# USB_SERIAL_QUAD.net
KiCad netlist of a schematic drawn in Altium Designer
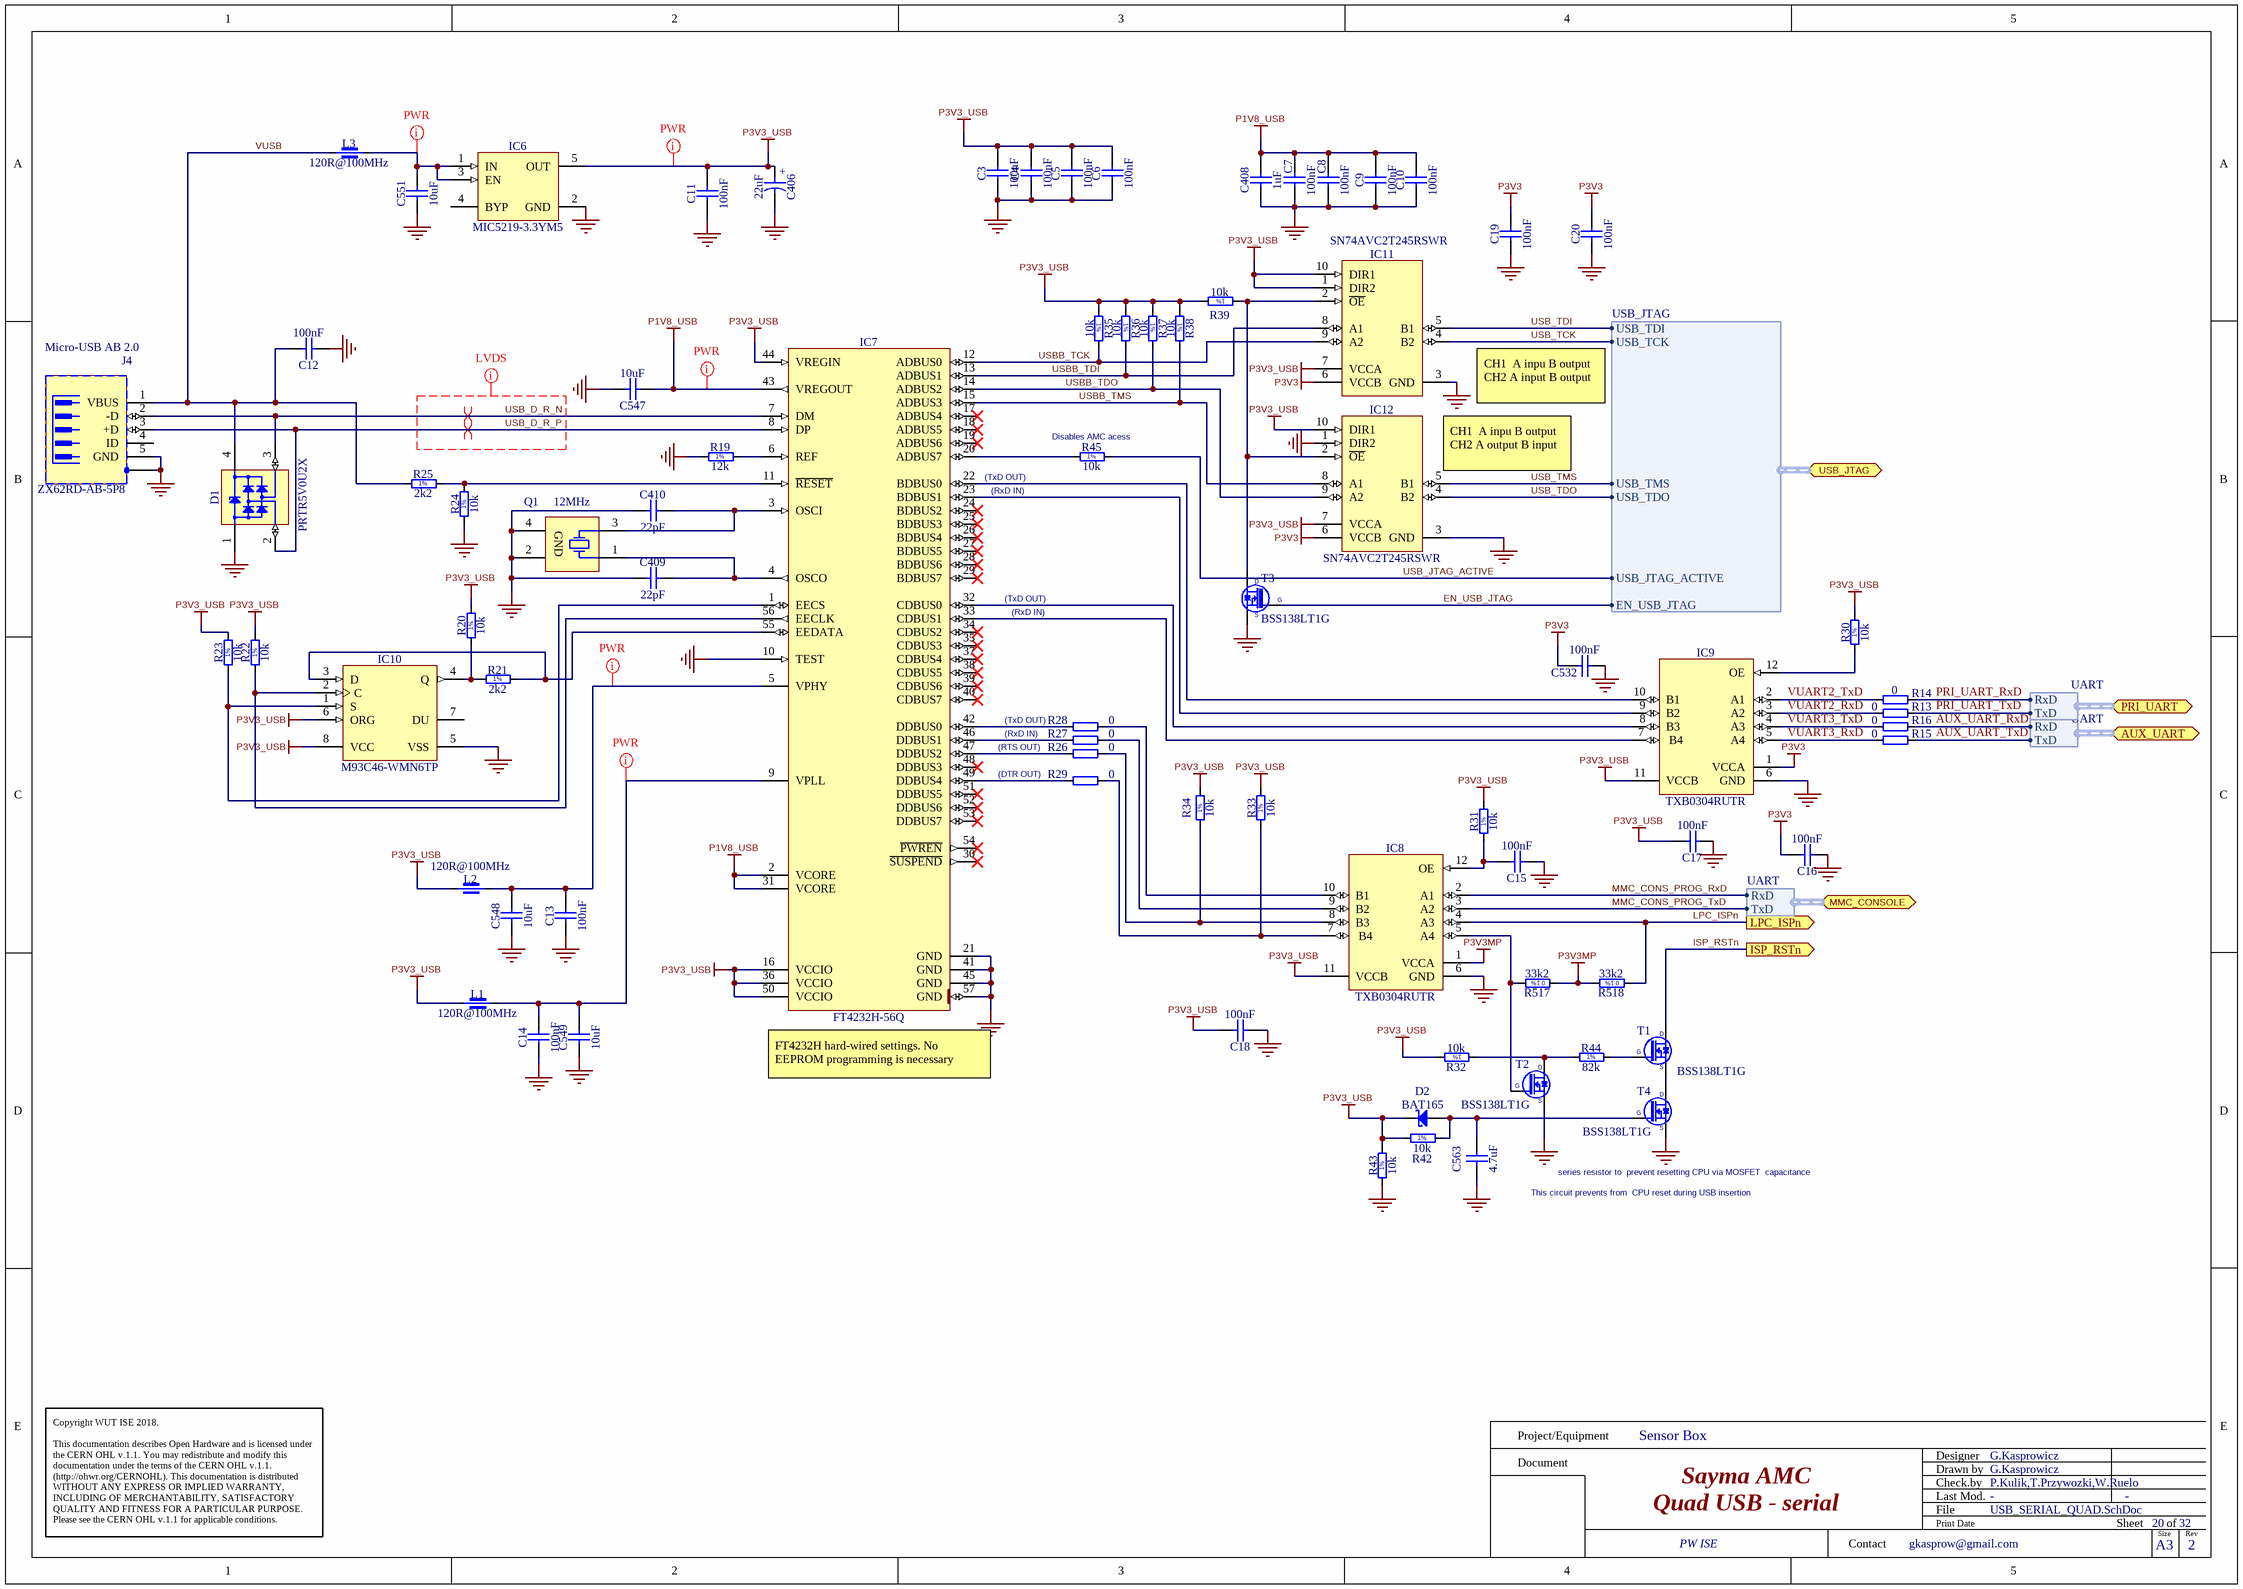
[diagram p0: USB_SERIAL_QUAD.SchDoc]

(export (version "E")
  (design (tool "Eeschema 10.0.6"))
  (components
    (comp (ref "C3")
      (value "100nF")
      (footprint "CAPC0603X33N")
      (description "Non-polarised capacitor")
      (fields
        (field (name "MANUFACTURER PART NUMBER") "CC0201_100NF_6.3V_10%_X5R")
        (field (name "MANUFACTURER") "GENERIC")
        (field (name "AUTHOR") "CERN DEM JLC")
      )
      (libsource (lib "Capacitors") (part "Capacitor - non polarized"))
    )
    (comp (ref "C4")
      (value "100nF")
      (footprint "CAPC0603X33N")
      (description "Non-polarised capacitor")
      (fields
        (field (name "MANUFACTURER PART NUMBER") "CC0201_100NF_6.3V_10%_X5R")
        (field (name "MANUFACTURER") "GENERIC")
        (field (name "AUTHOR") "CERN DEM JLC")
      )
      (libsource (lib "Capacitors") (part "Capacitor - non polarized"))
    )
    (comp (ref "C5")
      (value "100nF")
      (footprint "CAPC0603X33N")
      (description "Non-polarised capacitor")
      (fields
        (field (name "MANUFACTURER PART NUMBER") "CC0201_100NF_6.3V_10%_X5R")
        (field (name "MANUFACTURER") "GENERIC")
        (field (name "AUTHOR") "CERN DEM JLC")
      )
      (libsource (lib "Capacitors") (part "Capacitor - non polarized"))
    )
    (comp (ref "C6")
      (value "100nF")
      (footprint "CAPC0603X33N")
      (description "Non-polarised capacitor")
      (fields
        (field (name "MANUFACTURER PART NUMBER") "CC0201_100NF_6.3V_10%_X5R")
        (field (name "MANUFACTURER") "GENERIC")
        (field (name "AUTHOR") "CERN DEM JLC")
      )
      (libsource (lib "Capacitors") (part "Capacitor - non polarized"))
    )
    (comp (ref "C7")
      (value "100nF")
      (footprint "CAPC0603X33N")
      (description "Non-polarised capacitor")
      (fields
        (field (name "MANUFACTURER PART NUMBER") "CC0201_100NF_6.3V_10%_X5R")
        (field (name "MANUFACTURER") "GENERIC")
        (field (name "AUTHOR") "CERN DEM JLC")
      )
      (libsource (lib "Capacitors") (part "Capacitor - non polarized"))
    )
    (comp (ref "C8")
      (value "100nF")
      (footprint "CAPC0603X33N")
      (description "Non-polarised capacitor")
      (fields
        (field (name "MANUFACTURER PART NUMBER") "CC0201_100NF_6.3V_10%_X5R")
        (field (name "MANUFACTURER") "GENERIC")
        (field (name "AUTHOR") "CERN DEM JLC")
      )
      (libsource (lib "Capacitors") (part "Capacitor - non polarized"))
    )
    (comp (ref "C9")
      (value "100nF")
      (footprint "CAPC0603X33N")
      (description "Non-polarised capacitor")
      (fields
        (field (name "MANUFACTURER PART NUMBER") "CC0201_100NF_6.3V_10%_X5R")
        (field (name "MANUFACTURER") "GENERIC")
        (field (name "AUTHOR") "CERN DEM JLC")
      )
      (libsource (lib "Capacitors") (part "Capacitor - non polarized"))
    )
    (comp (ref "C10")
      (value "100nF")
      (footprint "CAPC0603X33N")
      (description "Non-polarised capacitor")
      (fields
        (field (name "MANUFACTURER PART NUMBER") "CC0201_100NF_6.3V_10%_X5R")
        (field (name "MANUFACTURER") "GENERIC")
        (field (name "AUTHOR") "CERN DEM JLC")
      )
      (libsource (lib "Capacitors") (part "Capacitor - non polarized"))
    )
    (comp (ref "C11")
      (value "100nF")
      (footprint "CAPC0603X33N")
      (description "Non-polarised capacitor")
      (fields
        (field (name "MANUFACTURER PART NUMBER") "CC0201_100NF_6.3V_10%_X5R")
        (field (name "MANUFACTURER") "GENERIC")
        (field (name "AUTHOR") "CERN DEM JLC")
      )
      (libsource (lib "Capacitors") (part "Capacitor - non polarized"))
    )
    (comp (ref "C12")
      (value "100nF")
      (footprint "CAPC0603X33N")
      (description "Non-polarised capacitor")
      (fields
        (field (name "MANUFACTURER PART NUMBER") "CC0201_100NF_6.3V_10%_X5R")
        (field (name "MANUFACTURER") "GENERIC")
        (field (name "AUTHOR") "CERN DEM JLC")
      )
      (libsource (lib "Capacitors") (part "Capacitor - non polarized"))
    )
    (comp (ref "C13")
      (value "100nF")
      (footprint "CAPC0603X33N")
      (description "Non-polarised capacitor")
      (fields
        (field (name "MANUFACTURER PART NUMBER") "CC0201_100NF_6.3V_10%_X5R")
        (field (name "MANUFACTURER") "GENERIC")
        (field (name "AUTHOR") "CERN DEM JLC")
      )
      (libsource (lib "Capacitors") (part "Capacitor - non polarized"))
    )
    (comp (ref "C14")
      (value "100nF")
      (footprint "CAPC0603X33N")
      (description "Non-polarised capacitor")
      (fields
        (field (name "MANUFACTURER PART NUMBER") "CC0201_100NF_6.3V_10%_X5R")
        (field (name "MANUFACTURER") "GENERIC")
        (field (name "AUTHOR") "CERN DEM JLC")
      )
      (libsource (lib "Capacitors") (part "Capacitor - non polarized"))
    )
    (comp (ref "C15")
      (value "100nF")
      (footprint "CAPC0603X33N")
      (description "Non-polarised capacitor")
      (fields
        (field (name "MANUFACTURER PART NUMBER") "CC0201_100NF_6.3V_10%_X5R")
        (field (name "MANUFACTURER") "GENERIC")
        (field (name "AUTHOR") "CERN DEM JLC")
      )
      (libsource (lib "Capacitors") (part "Capacitor - non polarized"))
    )
    (comp (ref "C16")
      (value "100nF")
      (footprint "CAPC0603X33N")
      (description "Non-polarised capacitor")
      (fields
        (field (name "MANUFACTURER PART NUMBER") "CC0201_100NF_6.3V_10%_X5R")
        (field (name "MANUFACTURER") "GENERIC")
        (field (name "AUTHOR") "CERN DEM JLC")
      )
      (libsource (lib "Capacitors") (part "Capacitor - non polarized"))
    )
    (comp (ref "C17")
      (value "100nF")
      (footprint "CAPC0603X33N")
      (description "Non-polarised capacitor")
      (fields
        (field (name "MANUFACTURER PART NUMBER") "CC0201_100NF_6.3V_10%_X5R")
        (field (name "MANUFACTURER") "GENERIC")
        (field (name "AUTHOR") "CERN DEM JLC")
      )
      (libsource (lib "Capacitors") (part "Capacitor - non polarized"))
    )
    (comp (ref "C18")
      (value "100nF")
      (footprint "CAPC0603X33N")
      (description "Non-polarised capacitor")
      (fields
        (field (name "MANUFACTURER PART NUMBER") "CC0201_100NF_6.3V_10%_X5R")
        (field (name "MANUFACTURER") "GENERIC")
        (field (name "AUTHOR") "CERN DEM JLC")
      )
      (libsource (lib "Capacitors") (part "Capacitor - non polarized"))
    )
    (comp (ref "C19")
      (value "100nF")
      (footprint "CAPC0603X33N")
      (description "Non-polarised capacitor")
      (fields
        (field (name "MANUFACTURER PART NUMBER") "CC0201_100NF_6.3V_10%_X5R")
        (field (name "MANUFACTURER") "GENERIC")
        (field (name "AUTHOR") "CERN DEM JLC")
      )
      (libsource (lib "Capacitors") (part "Capacitor - non polarized"))
    )
    (comp (ref "C20")
      (value "100nF")
      (footprint "CAPC0603X33N")
      (description "Non-polarised capacitor")
      (fields
        (field (name "MANUFACTURER PART NUMBER") "CC0201_100NF_6.3V_10%_X5R")
        (field (name "MANUFACTURER") "GENERIC")
        (field (name "AUTHOR") "CERN DEM JLC")
      )
      (libsource (lib "Capacitors") (part "Capacitor - non polarized"))
    )
    (comp (ref "C406")
      (value "22uF")
      (footprint "CAPMP3216X180N")
      (description "Polarised capacitor")
      (fields
        (field (name "MANUFACTURER PART NUMBER") "CTE3216-18_22UF_6.3V_10%_LESR0900")
        (field (name "MANUFACTURER") "GENERIC")
        (field (name "AUTHOR") "CERN DEM JLC")
      )
      (libsource (lib "Capacitors") (part "Capacitor - polarized"))
    )
    (comp (ref "C408")
      (value "1uF")
      (footprint "CAPC1005X55N")
      (description "Non-polarised capacitor")
      (fields
        (field (name "MANUFACTURER PART NUMBER") "CC0402_1UF_16V_10%_X5R")
        (field (name "MANUFACTURER") "GENERIC")
        (field (name "AUTHOR") "CERN DEM JLC")
      )
      (libsource (lib "Capacitors") (part "Capacitor - non polarized"))
    )
    (comp (ref "C409")
      (value "22pF")
      (footprint "CAPC1005X55N")
      (description "Non-polarised capacitor")
      (fields
        (field (name "MANUFACTURER PART NUMBER") "CC0402_22PF_50V_5%_C0G")
        (field (name "MANUFACTURER") "GENERIC")
        (field (name "AUTHOR") "CERN DEM JLC")
      )
      (libsource (lib "Capacitors") (part "Capacitor - non polarized"))
    )
    (comp (ref "C410")
      (value "22pF")
      (footprint "CAPC1005X55N")
      (description "Non-polarised capacitor")
      (fields
        (field (name "MANUFACTURER PART NUMBER") "CC0402_22PF_50V_5%_C0G")
        (field (name "MANUFACTURER") "GENERIC")
        (field (name "AUTHOR") "CERN DEM JLC")
      )
      (libsource (lib "Capacitors") (part "Capacitor - non polarized"))
    )
    (comp (ref "C532")
      (value "100nF")
      (footprint "CAPC0603X33N")
      (description "Non-polarised capacitor")
      (fields
        (field (name "MANUFACTURER PART NUMBER") "CC0201_100NF_6.3V_10%_X5R")
        (field (name "MANUFACTURER") "GENERIC")
        (field (name "AUTHOR") "CERN DEM JLC")
      )
      (libsource (lib "Capacitors") (part "Capacitor - non polarized"))
    )
    (comp (ref "C547")
      (value "10uF")
      (footprint "CAPC1608X87N")
      (description "Non-polarised capacitor")
      (fields
        (field (name "MANUFACTURER PART NUMBER") "CC0603_10uF_6.3V_20%_X5R")
        (field (name "MANUFACTURER") "GENERIC")
        (field (name "AUTHOR") "CERN DEM JLC")
      )
      (libsource (lib "Capacitors") (part "Capacitor - non polarized"))
    )
    (comp (ref "C548")
      (value "10uF")
      (footprint "CAPC1608X87N")
      (description "Non-polarised capacitor")
      (fields
        (field (name "MANUFACTURER PART NUMBER") "CC0603_10uF_6.3V_20%_X5R")
        (field (name "MANUFACTURER") "GENERIC")
        (field (name "AUTHOR") "CERN DEM JLC")
      )
      (libsource (lib "Capacitors") (part "Capacitor - non polarized"))
    )
    (comp (ref "C549")
      (value "10uF")
      (footprint "CAPC1608X87N")
      (description "Non-polarised capacitor")
      (fields
        (field (name "MANUFACTURER PART NUMBER") "CC0603_10uF_6.3V_20%_X5R")
        (field (name "MANUFACTURER") "GENERIC")
        (field (name "AUTHOR") "CERN DEM JLC")
      )
      (libsource (lib "Capacitors") (part "Capacitor - non polarized"))
    )
    (comp (ref "C551")
      (value "10uF")
      (footprint "CAPC1608X87N")
      (description "Non-polarised capacitor")
      (fields
        (field (name "MANUFACTURER PART NUMBER") "CC0603_10uF_6.3V_20%_X5R")
        (field (name "MANUFACTURER") "GENERIC")
        (field (name "AUTHOR") "CERN DEM JLC")
      )
      (libsource (lib "Capacitors") (part "Capacitor - non polarized"))
    )
    (comp (ref "C563")
      (value "4.7uF")
      (footprint "CAPC1709X95N")
      (description "Non-polarised capacitor")
      (fields
        (field (name "MANUFACTURER PART NUMBER") "CC0603_4.7UF_16V_10%_X5R")
        (field (name "MANUFACTURER") "GENERIC")
        (field (name "AUTHOR") "CERN DEM JLC")
      )
      (libsource (lib "Capacitors") (part "Capacitor - non polarized"))
    )
    (comp (ref "D1")
      (value "PRTR5V0U2X")
      (footprint "SOT190P230X110-4N")
      (description "Ultra Low Capacitance Double Rail-to-Rail ESD Protection Diode")
      (fields
        (field (name "MANUFACTURER") "NXP SEMICONDUCTORS")
        (field (name "VOLTAGE") "5.5V")
        (field (name "AUTHOR") "CERN DEM JLC")
      )
      (libsource (lib "ICs And Semiconductors") (part "PRTR5V0U2X"))
    )
    (comp (ref "D2")
      (value "BAT165")
      (footprint "SOD2512X110N")
      (description "Schottky Diode")
      (fields
        (field (name "MANUFACTURER") "INFINEON")
        (field (name "VOLTAGE") "40V")
        (field (name "AUTHOR") "CERN DEM JLC")
      )
      (libsource (lib "ICs And Semiconductors") (part "Diode Schottky"))
    )
    (comp (ref "IC6")
      (value "MIC5219-3.3YM5")
      (footprint "SOT95P280X145-5N")
      (description "500mA Peak Output LDO Regulator")
      (fields (field (name "MANUFACTURER") "MICROCHIP TECHNOLOGY") (field (name "AUTHOR") "CERN DEM WB"))
      (libsource (lib "ICs And Semiconductors") (part "MIC5219-X.XYM5"))
    )
    (comp (ref "IC7")
      (value "FT4232H-56Q")
      (footprint "QFN50P800X800X100-57N-S620")
      (description "Quad High Speed USB to Multipurpose UART/MPSSE IC")
      (fields
        (field (name "MANUFACTURER") "FUTURE TECHNOLOGY DEVICES INTERNATIONAL (FTDI)")
        (field (name "AUTHOR") "CERN DEM JLC")
      )
      (libsource (lib "ICs And Semiconductors") (part "FT4232H-56Q"))
    )
    (comp (ref "IC8")
      (value "TXB0304RUTR")
      (footprint "TEXAS_RUT (R-PUQFN-N12)")
      (description "4-bit Bidirectional Auto-direction Sensing Translator with Fully Symmetric 0.9V to 3.6V Range")
      (fields (field (name "MANUFACTURER") "TEXAS INSTRUMENTS") (field (name "AUTHOR") "CERN DEM JLC"))
      (libsource (lib "ICs And Semiconductors") (part "TXB0304RUTR"))
    )
    (comp (ref "IC9")
      (value "TXB0304RUTR")
      (footprint "TEXAS_RUT (R-PUQFN-N12)")
      (description "4-bit Bidirectional Auto-direction Sensing Translator with Fully Symmetric 0.9V to 3.6V Range")
      (fields (field (name "MANUFACTURER") "TEXAS INSTRUMENTS") (field (name "AUTHOR") "CERN DEM JLC"))
      (libsource (lib "ICs And Semiconductors") (part "TXB0304RUTR"))
    )
    (comp (ref "IC10")
      (value "M93C46-WMN6TP")
      (footprint "SOIC127P600X175-8N")
      (description "2.5 to 5.5 V, 1Kb (128x8) Serial Microwire Bus EEPROM")
      (fields (field (name "MANUFACTURER") "ST MICROELECTRONICS") (field (name "AUTHOR") "CERN DEM JLC"))
      (libsource (lib "ICs And Semiconductors") (part "M93C46-WMN6TP"))
    )
    (comp (ref "IC11")
      (value "SN74AVC2T245RSWR")
      (footprint "QFN40P140X180X55-10N")
      (description "Dual-Bit Dual-Supply Bus Transceiver With Configurable Voltage Translation and 3-State Outputs")
      (fields (field (name "MANUFACTURER") "TEXAS INSTRUMENTS") (field (name "AUTHOR") "CERN DEM JLC"))
      (libsource (lib "ICs And Semiconductors") (part "742T245"))
    )
    (comp (ref "IC12")
      (value "SN74AVC2T245RSWR")
      (footprint "QFN40P140X180X55-10N")
      (description "Dual-Bit Dual-Supply Bus Transceiver With Configurable Voltage Translation and 3-State Outputs")
      (fields (field (name "MANUFACTURER") "TEXAS INSTRUMENTS") (field (name "AUTHOR") "CERN DEM JLC"))
      (libsource (lib "ICs And Semiconductors") (part "742T245"))
    )
    (comp (ref "J4")
      (value "Micro-USB AB 2.0")
      (footprint "HIROSE_ZX62RD-AB-5P8")
      (description "5 Pin + 1 Shield USB Receptacle")
      (fields
        (field (name "MANUFACTURER PART NUMBER") "ZX62RD-AB-5P8")
        (field (name "MANUFACTURER") "HIROSE (HRS)")
        (field (name "PART NUMBER") "HIROSE_ZX62RD-AB-5P8")
        (field (name "AUTHOR") "CERN DEM JLC")
      )
      (libsource (lib "Connectors") (part "Connector USB 5 Pin + 1Shield"))
    )
    (comp (ref "L1")
      (value "120R@100MHz")
      (footprint "INDC1608X65N")
      (fields
        (field (name "MANUFACTURER PART NUMBER") "BLM18SG121TN1D")
        (field (name "MANUFACTURER") "MURATA")
        (field (name "PART NUMBER") "IND0603_MURATA_BLM18SG121TN1D")
        (field (name "AUTHOR") "CERN DEM JLC")
      )
      (libsource (lib "Inductors & Transformers") (part "Ferrite Bead"))
    )
    (comp (ref "L2")
      (value "120R@100MHz")
      (footprint "INDC1608X65N")
      (fields
        (field (name "MANUFACTURER PART NUMBER") "BLM18SG121TN1D")
        (field (name "MANUFACTURER") "MURATA")
        (field (name "PART NUMBER") "IND0603_MURATA_BLM18SG121TN1D")
        (field (name "AUTHOR") "CERN DEM JLC")
      )
      (libsource (lib "Inductors & Transformers") (part "Ferrite Bead"))
    )
    (comp (ref "L3")
      (value "120R@100MHz")
      (footprint "INDC1608X65N")
      (fields
        (field (name "MANUFACTURER PART NUMBER") "BLM18SG121TN1D")
        (field (name "MANUFACTURER") "MURATA")
        (field (name "PART NUMBER") "IND0603_MURATA_BLM18SG121TN1D")
        (field (name "AUTHOR") "CERN DEM JLC")
      )
      (libsource (lib "Inductors & Transformers") (part "Ferrite Bead"))
    )
    (comp (ref "Q1")
      (value "12MHz")
      (footprint "XTAL_TXC_7M")
      (description "Crystal 4 pins 1=XTAL Control 2=GND3=XTAL 4=GND")
      (fields
        (field (name "MANUFACTURER PART NUMBER") "7M-12.000MAAJ-T")
        (field (name "MANUFACTURER") "TXC CORPORATION")
        (field (name "AUTHOR") "CERN DEM JLC")
      )
      (libsource (lib "ICs And Semiconductors") (part "Quartz Crystal 1X 2GND 3X 4GND"))
    )
    (comp (ref "R13")
      (value "0")
      (footprint "RESC1005X40N")
      (description "Resistor")
      (fields
        (field (name "MANUFACTURER PART NUMBER") "R0402_0R_JUMPER")
        (field (name "MANUFACTURER") "GENERIC")
        (field (name "AUTHOR") "CERN DEM JLC")
      )
      (libsource (lib "Resistors") (part "Resistor"))
    )
    (comp (ref "R14")
      (value "0")
      (footprint "RESC1005X40N")
      (description "Resistor")
      (fields
        (field (name "MANUFACTURER PART NUMBER") "R0402_0R_JUMPER")
        (field (name "MANUFACTURER") "GENERIC")
        (field (name "AUTHOR") "CERN DEM JLC")
      )
      (libsource (lib "Resistors") (part "Resistor"))
    )
    (comp (ref "R15")
      (value "0")
      (footprint "RESC1005X40N")
      (description "Resistor")
      (fields
        (field (name "MANUFACTURER PART NUMBER") "R0402_0R_JUMPER")
        (field (name "MANUFACTURER") "GENERIC")
        (field (name "AUTHOR") "CERN DEM JLC")
      )
      (libsource (lib "Resistors") (part "Resistor"))
    )
    (comp (ref "R16")
      (value "0")
      (footprint "RESC1005X40N")
      (description "Resistor")
      (fields
        (field (name "MANUFACTURER PART NUMBER") "R0402_0R_JUMPER")
        (field (name "MANUFACTURER") "GENERIC")
        (field (name "AUTHOR") "CERN DEM JLC")
      )
      (libsource (lib "Resistors") (part "Resistor"))
    )
    (comp (ref "R19")
      (value "12k")
      (footprint "RESC1005X40N")
      (description "Resistor - 1%")
      (fields
        (field (name "MANUFACTURER PART NUMBER") "R0402_12K_1%_0.0625W_100PPM")
        (field (name "MANUFACTURER") "GENERIC")
        (field (name "AUTHOR") "CERN DEM JLC")
      )
      (libsource (lib "Resistors") (part "Resistor - 1%"))
    )
    (comp (ref "R20")
      (value "10k")
      (footprint "RESC1005X40N")
      (description "Resistor - 1%")
      (fields
        (field (name "MANUFACTURER PART NUMBER") "R0402_10K_1%_0.0625W_100PPM")
        (field (name "MANUFACTURER") "GENERIC")
        (field (name "AUTHOR") "CERN DEM JLC")
      )
      (libsource (lib "Resistors") (part "Resistor - 1%"))
    )
    (comp (ref "R21")
      (value "2k2")
      (footprint "RESC1005X40N")
      (description "Resistor - 1%")
      (fields
        (field (name "MANUFACTURER PART NUMBER") "R0402_2K2_1%_0.0625W_100PPM")
        (field (name "MANUFACTURER") "GENERIC")
        (field (name "AUTHOR") "CERN DEM JLC")
      )
      (libsource (lib "Resistors") (part "Resistor - 1%"))
    )
    (comp (ref "R22")
      (value "10k")
      (footprint "RESC1005X40N")
      (description "Resistor - 1%")
      (fields
        (field (name "MANUFACTURER PART NUMBER") "R0402_10K_1%_0.0625W_100PPM")
        (field (name "MANUFACTURER") "GENERIC")
        (field (name "AUTHOR") "CERN DEM JLC")
      )
      (libsource (lib "Resistors") (part "Resistor - 1%"))
    )
    (comp (ref "R23")
      (value "10k")
      (footprint "RESC1005X40N")
      (description "Resistor - 1%")
      (fields
        (field (name "MANUFACTURER PART NUMBER") "R0402_10K_1%_0.0625W_100PPM")
        (field (name "MANUFACTURER") "GENERIC")
        (field (name "AUTHOR") "CERN DEM JLC")
      )
      (libsource (lib "Resistors") (part "Resistor - 1%"))
    )
    (comp (ref "R24")
      (value "10k")
      (footprint "RESC1005X40N")
      (description "Resistor - 1%")
      (fields
        (field (name "MANUFACTURER PART NUMBER") "R0402_10K_1%_0.0625W_100PPM")
        (field (name "MANUFACTURER") "GENERIC")
        (field (name "AUTHOR") "CERN DEM JLC")
      )
      (libsource (lib "Resistors") (part "Resistor - 1%"))
    )
    (comp (ref "R25")
      (value "2k2")
      (footprint "RESC1005X40N")
      (description "Resistor - 1%")
      (fields
        (field (name "MANUFACTURER PART NUMBER") "R0402_2K2_1%_0.0625W_100PPM")
        (field (name "MANUFACTURER") "GENERIC")
        (field (name "AUTHOR") "CERN DEM JLC")
      )
      (libsource (lib "Resistors") (part "Resistor - 1%"))
    )
    (comp (ref "R26")
      (value "0")
      (footprint "RESC1005X40N")
      (description "Resistor")
      (fields
        (field (name "MANUFACTURER PART NUMBER") "R0402_0R_JUMPER")
        (field (name "MANUFACTURER") "GENERIC")
        (field (name "AUTHOR") "CERN DEM JLC")
      )
      (libsource (lib "Resistors") (part "Resistor"))
    )
    (comp (ref "R27")
      (value "0")
      (footprint "RESC1005X40N")
      (description "Resistor")
      (fields
        (field (name "MANUFACTURER PART NUMBER") "R0402_0R_JUMPER")
        (field (name "MANUFACTURER") "GENERIC")
        (field (name "AUTHOR") "CERN DEM JLC")
      )
      (libsource (lib "Resistors") (part "Resistor"))
    )
    (comp (ref "R28")
      (value "0")
      (footprint "RESC1005X40N")
      (description "Resistor")
      (fields
        (field (name "MANUFACTURER PART NUMBER") "R0402_0R_JUMPER")
        (field (name "MANUFACTURER") "GENERIC")
        (field (name "AUTHOR") "CERN DEM JLC")
      )
      (libsource (lib "Resistors") (part "Resistor"))
    )
    (comp (ref "R29")
      (value "0")
      (footprint "RESC1005X40N")
      (description "Resistor")
      (fields
        (field (name "MANUFACTURER PART NUMBER") "R0402_0R_JUMPER")
        (field (name "MANUFACTURER") "GENERIC")
        (field (name "AUTHOR") "CERN DEM JLC")
      )
      (libsource (lib "Resistors") (part "Resistor"))
    )
    (comp (ref "R30")
      (value "10k")
      (footprint "RESC1005X40N")
      (description "Resistor - 1%")
      (fields
        (field (name "MANUFACTURER PART NUMBER") "R0402_10K_1%_0.0625W_100PPM")
        (field (name "MANUFACTURER") "GENERIC")
        (field (name "AUTHOR") "CERN DEM JLC")
      )
      (libsource (lib "Resistors") (part "Resistor - 1%"))
    )
    (comp (ref "R31")
      (value "10k")
      (footprint "RESC1005X40N")
      (description "Resistor - 1%")
      (fields
        (field (name "MANUFACTURER PART NUMBER") "R0402_10K_1%_0.0625W_100PPM")
        (field (name "MANUFACTURER") "GENERIC")
        (field (name "AUTHOR") "CERN DEM JLC")
      )
      (libsource (lib "Resistors") (part "Resistor - 1%"))
    )
    (comp (ref "R32")
      (value "10k")
      (footprint "RESC1005X40N")
      (description "Resistor - 1%")
      (fields
        (field (name "MANUFACTURER PART NUMBER") "R0402_10K_1%_0.0625W_100PPM")
        (field (name "MANUFACTURER") "GENERIC")
        (field (name "AUTHOR") "CERN DEM JLC")
      )
      (libsource (lib "Resistors") (part "Resistor - 1%"))
    )
    (comp (ref "R33")
      (value "10k")
      (footprint "RESC1005X40N")
      (description "Resistor - 1%")
      (fields
        (field (name "MANUFACTURER PART NUMBER") "R0402_10K_1%_0.0625W_100PPM")
        (field (name "MANUFACTURER") "GENERIC")
        (field (name "AUTHOR") "CERN DEM JLC")
      )
      (libsource (lib "Resistors") (part "Resistor - 1%"))
    )
    (comp (ref "R34")
      (value "10k")
      (footprint "RESC1005X40N")
      (description "Resistor - 1%")
      (fields
        (field (name "MANUFACTURER PART NUMBER") "R0402_10K_1%_0.0625W_100PPM")
        (field (name "MANUFACTURER") "GENERIC")
        (field (name "AUTHOR") "CERN DEM JLC")
      )
      (libsource (lib "Resistors") (part "Resistor - 1%"))
    )
    (comp (ref "R35")
      (value "10k")
      (footprint "RESC1005X40N")
      (description "Resistor - 1%")
      (fields
        (field (name "MANUFACTURER PART NUMBER") "R0402_10K_1%_0.0625W_100PPM")
        (field (name "MANUFACTURER") "GENERIC")
        (field (name "AUTHOR") "CERN DEM JLC")
      )
      (libsource (lib "Resistors") (part "Resistor - 1%"))
    )
    (comp (ref "R36")
      (value "10k")
      (footprint "RESC1005X40N")
      (description "Resistor - 1%")
      (fields
        (field (name "MANUFACTURER PART NUMBER") "R0402_10K_1%_0.0625W_100PPM")
        (field (name "MANUFACTURER") "GENERIC")
        (field (name "AUTHOR") "CERN DEM JLC")
      )
      (libsource (lib "Resistors") (part "Resistor - 1%"))
    )
    (comp (ref "R37")
      (value "10k")
      (footprint "RESC1005X40N")
      (description "Resistor - 1%")
      (fields
        (field (name "MANUFACTURER PART NUMBER") "R0402_10K_1%_0.0625W_100PPM")
        (field (name "MANUFACTURER") "GENERIC")
        (field (name "AUTHOR") "CERN DEM JLC")
      )
      (libsource (lib "Resistors") (part "Resistor - 1%"))
    )
    (comp (ref "R38")
      (value "10k")
      (footprint "RESC1005X40N")
      (description "Resistor - 1%")
      (fields
        (field (name "MANUFACTURER PART NUMBER") "R0402_10K_1%_0.0625W_100PPM")
        (field (name "MANUFACTURER") "GENERIC")
        (field (name "AUTHOR") "CERN DEM JLC")
      )
      (libsource (lib "Resistors") (part "Resistor - 1%"))
    )
    (comp (ref "R39")
      (value "10k")
      (footprint "RESC1005X40N")
      (description "Resistor - 1%")
      (fields
        (field (name "MANUFACTURER PART NUMBER") "R0402_10K_1%_0.0625W_100PPM")
        (field (name "MANUFACTURER") "GENERIC")
        (field (name "AUTHOR") "CERN DEM JLC")
      )
      (libsource (lib "Resistors") (part "Resistor - 1%"))
    )
    (comp (ref "R42")
      (value "10k")
      (footprint "RESC1005X40N")
      (description "Resistor - 1%")
      (fields
        (field (name "MANUFACTURER PART NUMBER") "R0402_10K_1%_0.0625W_100PPM")
        (field (name "MANUFACTURER") "GENERIC")
        (field (name "AUTHOR") "CERN DEM JLC")
      )
      (libsource (lib "Resistors") (part "Resistor - 1%"))
    )
    (comp (ref "R43")
      (value "10k")
      (footprint "RESC1005X40N")
      (description "Resistor - 1%")
      (fields
        (field (name "MANUFACTURER PART NUMBER") "R0402_10K_1%_0.0625W_100PPM")
        (field (name "MANUFACTURER") "GENERIC")
        (field (name "AUTHOR") "CERN DEM JLC")
      )
      (libsource (lib "Resistors") (part "Resistor - 1%"))
    )
    (comp (ref "R44")
      (value "82k")
      (footprint "RESC1005X40N")
      (description "Resistor - 1%")
      (fields
        (field (name "MANUFACTURER PART NUMBER") "R0402_82K_1%_0.0625W_100PPM")
        (field (name "MANUFACTURER") "GENERIC")
        (field (name "AUTHOR") "CERN DEM JLC")
      )
      (libsource (lib "Resistors") (part "Resistor - 1%"))
    )
    (comp (ref "R45")
      (value "10k")
      (footprint "RESC1005X40N")
      (description "Resistor - 1%")
      (fields
        (field (name "MANUFACTURER PART NUMBER") "R0402_10K_1%_0.0625W_100PPM")
        (field (name "MANUFACTURER") "GENERIC")
        (field (name "AUTHOR") "CERN DEM JLC")
      )
      (libsource (lib "Resistors") (part "Resistor - 1%"))
    )
    (comp (ref "R517")
      (value "33k2")
      (footprint "RESC1608X55N")
      (description "Resistor - 0.1%")
      (fields
        (field (name "MANUFACTURER PART NUMBER") "R0603_33K2_0.1%_0.063W_10PPM")
        (field (name "MANUFACTURER") "GENERIC")
        (field (name "AUTHOR") "CERN DEM JLC")
      )
      (libsource (lib "Resistors") (part "Resistor - 0.1%"))
    )
    (comp (ref "R518")
      (value "33k2")
      (footprint "RESC1608X55N")
      (description "Resistor - 0.1%")
      (fields
        (field (name "MANUFACTURER PART NUMBER") "R0603_33K2_0.1%_0.063W_10PPM")
        (field (name "MANUFACTURER") "GENERIC")
        (field (name "AUTHOR") "CERN DEM JLC")
      )
      (libsource (lib "Resistors") (part "Resistor - 0.1%"))
    )
    (comp (ref "T1")
      (value "BSS138LT1G")
      (footprint "SOT95P240X110-3N")
      (description "N-CHANNEL MOSFET WITH DIODE")
      (fields (field (name "MANUFACTURER") "ON SEMICONDUCTOR") (field (name "AUTHOR") "CERN DEM JLC"))
      (libsource (lib "ICs And Semiconductors") (part "N-MOSFET-D 1G 2S 3D"))
    )
    (comp (ref "T2")
      (value "BSS138LT1G")
      (footprint "SOT95P240X110-3N")
      (description "N-CHANNEL MOSFET WITH DIODE")
      (fields (field (name "MANUFACTURER") "ON SEMICONDUCTOR") (field (name "AUTHOR") "CERN DEM JLC"))
      (libsource (lib "ICs And Semiconductors") (part "N-MOSFET-D 1G 2S 3D"))
    )
    (comp (ref "T3")
      (value "BSS138LT1G")
      (footprint "SOT95P240X110-3N")
      (description "N-CHANNEL MOSFET WITH DIODE")
      (fields (field (name "MANUFACTURER") "ON SEMICONDUCTOR") (field (name "AUTHOR") "CERN DEM JLC"))
      (libsource (lib "") (part "N-MOSFET-D 1G 2S 3D_1"))
    )
    (comp (ref "T4")
      (value "BSS138LT1G")
      (footprint "SOT95P240X110-3N")
      (description "N-CHANNEL MOSFET WITH DIODE")
      (fields (field (name "MANUFACTURER") "ON SEMICONDUCTOR") (field (name "AUTHOR") "CERN DEM JLC"))
      (libsource (lib "ICs And Semiconductors") (part "N-MOSFET-D 1G 2S 3D"))
    )
  )
  (nets
    (net (code "4") (name "/AUX_UART_RxD") (class "Default")
      (node (ref "R16") (pin "1") (pinfunction "1_1") (pintype "passive"))
    )
    (net (code "5") (name "/AUX_UART_TxD") (class "Default")
      (node (ref "R15") (pin "1") (pinfunction "1_1") (pintype "passive"))
    )
    (net (code "6") (name "/EN_USB_JTAG") (class "Default")
      (node (ref "T3") (pin "1") (pinfunction "G_1") (pintype "passive"))
    )
    (net (code "7") (name "/ISP_RSTn") (class "Default")
      (node (ref "T1") (pin "3") (pinfunction "D_3") (pintype "passive"))
    )
    (net (code "8") (name "/LPC_ISPn") (class "Default")
      (node (ref "IC8") (pin "4") (pinfunction "A3_4") (pintype "bidirectional"))
      (node (ref "R518") (pin "1") (pinfunction "1_1") (pintype "passive"))
    )
    (net (code "9") (name "/MMC_CONS_PROG_RxD") (class "Default")
      (node (ref "IC8") (pin "2") (pinfunction "A1_2") (pintype "bidirectional"))
    )
    (net (code "10") (name "/MMC_CONS_PROG_TxD") (class "Default")
      (node (ref "IC8") (pin "3") (pinfunction "A2_3") (pintype "bidirectional"))
    )
    (net (code "11") (name "/PRI_UART_RxD") (class "Default")
      (node (ref "R14") (pin "1") (pinfunction "1_1") (pintype "passive"))
    )
    (net (code "12") (name "/PRI_UART_TxD") (class "Default")
      (node (ref "R13") (pin "1") (pinfunction "1_1") (pintype "passive"))
    )
    (net (code "14") (name "/USBB_TCK") (class "Default")
      (node (ref "IC11") (pin "9") (pinfunction "A2_9") (pintype "bidirectional"))
      (node (ref "IC7") (pin "12") (pinfunction "ADBUS0_12") (pintype "bidirectional"))
      (node (ref "R35") (pin "2") (pinfunction "2_2") (pintype "passive"))
    )
    (net (code "15") (name "/USBB_TDI") (class "Default")
      (node (ref "IC11") (pin "8") (pinfunction "A1_8") (pintype "bidirectional"))
      (node (ref "IC7") (pin "13") (pinfunction "ADBUS1_13") (pintype "bidirectional"))
      (node (ref "R36") (pin "2") (pinfunction "2_2") (pintype "passive"))
    )
    (net (code "16") (name "/USBB_TDO") (class "Default")
      (node (ref "IC12") (pin "9") (pinfunction "A2_9") (pintype "bidirectional"))
      (node (ref "IC7") (pin "14") (pinfunction "ADBUS2_14") (pintype "bidirectional"))
      (node (ref "R37") (pin "2") (pinfunction "2_2") (pintype "passive"))
    )
    (net (code "17") (name "/USBB_TMS") (class "Default")
      (node (ref "IC12") (pin "8") (pinfunction "A1_8") (pintype "bidirectional"))
      (node (ref "IC7") (pin "15") (pinfunction "ADBUS3_15") (pintype "bidirectional"))
      (node (ref "R38") (pin "2") (pinfunction "2_2") (pintype "passive"))
    )
    (net (code "18") (name "/USB_D_R_N") (class "Default")
      (node (ref "D1") (pin "3") (pinfunction "I/O2_3") (pintype "bidirectional"))
      (node (ref "IC7") (pin "7") (pinfunction "DM_7") (pintype "input"))
      (node (ref "J4") (pin "2") (pinfunction "-D_2") (pintype "bidirectional"))
    )
    (net (code "19") (name "/USB_D_R_P") (class "Default")
      (node (ref "D1") (pin "2") (pinfunction "I/O1_2") (pintype "bidirectional"))
      (node (ref "IC7") (pin "8") (pinfunction "DP_8") (pintype "input"))
      (node (ref "J4") (pin "3") (pinfunction "+D_3") (pintype "bidirectional"))
    )
    (net (code "20") (name "/USB_JTAG_ACTIVE") (class "Default")
      (node (ref "R45") (pin "2") (pinfunction "2_2") (pintype "passive"))
    )
    (net (code "21") (name "/USB_TCK") (class "Default")
      (node (ref "IC11") (pin "4") (pinfunction "B2_4") (pintype "bidirectional"))
    )
    (net (code "22") (name "/USB_TDI") (class "Default")
      (node (ref "IC11") (pin "5") (pinfunction "B1_5") (pintype "bidirectional"))
    )
    (net (code "23") (name "/USB_TDO") (class "Default")
      (node (ref "IC12") (pin "4") (pinfunction "B2_4") (pintype "bidirectional"))
    )
    (net (code "24") (name "/USB_TMS") (class "Default")
      (node (ref "IC12") (pin "5") (pinfunction "B1_5") (pintype "bidirectional"))
    )
    (net (code "25") (name "/VUART2_RxD") (class "Default")
      (node (ref "IC9") (pin "3") (pinfunction "A2_3") (pintype "bidirectional"))
      (node (ref "R13") (pin "2") (pinfunction "2_2") (pintype "passive"))
    )
    (net (code "26") (name "/VUART2_TxD") (class "Default")
      (node (ref "IC9") (pin "2") (pinfunction "A1_2") (pintype "bidirectional"))
      (node (ref "R14") (pin "2") (pinfunction "2_2") (pintype "passive"))
    )
    (net (code "27") (name "/VUART3_RxD") (class "Default")
      (node (ref "IC9") (pin "5") (pinfunction "A4_5") (pintype "bidirectional"))
      (node (ref "R15") (pin "2") (pinfunction "2_2") (pintype "passive"))
    )
    (net (code "28") (name "/VUART3_TxD") (class "Default")
      (node (ref "IC9") (pin "4") (pinfunction "A3_4") (pintype "bidirectional"))
      (node (ref "R16") (pin "2") (pinfunction "2_2") (pintype "passive"))
    )
    (net (code "29") (name "/VUSB") (class "Default")
      (node (ref "C12") (pin "2") (pinfunction "2_2") (pintype "passive"))
      (node (ref "D1") (pin "4") (pinfunction "VCC_4") (pintype "power_in"))
      (node (ref "J4") (pin "1") (pinfunction "VBUS_1") (pintype "power_in"))
      (node (ref "L3") (pin "1") (pinfunction "1_1") (pintype "passive"))
      (node (ref "R25") (pin "1") (pinfunction "1_1") (pintype "passive"))
    )
    (net (code "32") (name "GND") (class "Default")
      (node (ref "C10") (pin "1") (pinfunction "1_1") (pintype "passive"))
      (node (ref "C11") (pin "1") (pinfunction "1_1") (pintype "passive"))
      (node (ref "C12") (pin "1") (pinfunction "1_1") (pintype "passive"))
      (node (ref "C13") (pin "1") (pinfunction "1_1") (pintype "passive"))
      (node (ref "C14") (pin "1") (pinfunction "1_1") (pintype "passive"))
      (node (ref "C15") (pin "1") (pinfunction "1_1") (pintype "passive"))
      (node (ref "C16") (pin "1") (pinfunction "1_1") (pintype "passive"))
      (node (ref "C17") (pin "1") (pinfunction "1_1") (pintype "passive"))
      (node (ref "C18") (pin "1") (pinfunction "1_1") (pintype "passive"))
      (node (ref "C19") (pin "1") (pinfunction "1_1") (pintype "passive"))
      (node (ref "C20") (pin "1") (pinfunction "1_1") (pintype "passive"))
      (node (ref "C3") (pin "1") (pinfunction "1_1") (pintype "passive"))
      (node (ref "C4") (pin "1") (pinfunction "1_1") (pintype "passive"))
      (node (ref "C406") (pin "2") (pinfunction "2_2") (pintype "passive"))
      (node (ref "C408") (pin "2") (pinfunction "2_2") (pintype "passive"))
      (node (ref "C409") (pin "1") (pinfunction "1_1") (pintype "passive"))
      (node (ref "C410") (pin "1") (pinfunction "1_1") (pintype "passive"))
      (node (ref "C5") (pin "1") (pinfunction "1_1") (pintype "passive"))
      (node (ref "C532") (pin "1") (pinfunction "1_1") (pintype "passive"))
      (node (ref "C547") (pin "2") (pinfunction "2_2") (pintype "passive"))
      (node (ref "C548") (pin "1") (pinfunction "1_1") (pintype "passive"))
      (node (ref "C549") (pin "1") (pinfunction "1_1") (pintype "passive"))
      (node (ref "C551") (pin "1") (pinfunction "1_1") (pintype "passive"))
      (node (ref "C563") (pin "1") (pinfunction "1_1") (pintype "passive"))
      (node (ref "C6") (pin "1") (pinfunction "1_1") (pintype "passive"))
      (node (ref "C7") (pin "1") (pinfunction "1_1") (pintype "passive"))
      (node (ref "C8") (pin "1") (pinfunction "1_1") (pintype "passive"))
      (node (ref "C9") (pin "1") (pinfunction "1_1") (pintype "passive"))
      (node (ref "D1") (pin "1") (pinfunction "GND_1") (pintype "power_in"))
      (node (ref "IC10") (pin "5") (pinfunction "VSS_5") (pintype "power_in"))
      (node (ref "IC11") (pin "3") (pinfunction "GND_3") (pintype "power_in"))
      (node (ref "IC12") (pin "1") (pinfunction "DIR2_1") (pintype "input"))
      (node (ref "IC12") (pin "3") (pinfunction "GND_3") (pintype "power_in"))
      (node (ref "IC6") (pin "2") (pinfunction "GND_2") (pintype "power_in"))
      (node (ref "IC7") (pin "10") (pinfunction "TEST_10") (pintype "input"))
      (node (ref "IC7") (pin "21") (pinfunction "GND_21") (pintype "power_in"))
      (node (ref "IC7") (pin "41") (pinfunction "GND_41") (pintype "power_in"))
      (node (ref "IC7") (pin "45") (pinfunction "GND_45") (pintype "power_in"))
      (node (ref "IC7") (pin "57") (pinfunction "GND_57") (pintype "bidirectional"))
      (node (ref "IC8") (pin "6") (pinfunction "GND_6") (pintype "power_in"))
      (node (ref "IC9") (pin "6") (pinfunction "GND_6") (pintype "power_in"))
      (node (ref "J4") (pin "5") (pinfunction "GND_5") (pintype "power_in"))
      (node (ref "J4") (pin "6") (pinfunction "SH_6") (pintype "power_in"))
      (node (ref "Q1") (pin "2") (pinfunction "GND_2") (pintype "power_in"))
      (node (ref "Q1") (pin "4") (pinfunction "GND_4") (pintype "power_in"))
      (node (ref "R19") (pin "1") (pinfunction "1_1") (pintype "passive"))
      (node (ref "R24") (pin "1") (pinfunction "1_1") (pintype "passive"))
      (node (ref "R43") (pin "1") (pinfunction "1_1") (pintype "passive"))
      (node (ref "T2") (pin "2") (pinfunction "S_2") (pintype "passive"))
      (node (ref "T3") (pin "2") (pinfunction "S_2") (pintype "passive"))
      (node (ref "T4") (pin "2") (pinfunction "S_2") (pintype "passive"))
    )
    (net (code "33") (name "Net-(D2-A)") (class "Default")
      (node (ref "C563") (pin "2") (pinfunction "2_2") (pintype "passive"))
      (node (ref "D2") (pin "2") (pinfunction "A_2") (pintype "passive"))
      (node (ref "R42") (pin "2") (pinfunction "2_2") (pintype "passive"))
      (node (ref "T4") (pin "1") (pinfunction "G_1") (pintype "passive"))
    )
    (net (code "34") (name "Net-(IC6-EN)") (class "Default")
      (node (ref "C551") (pin "2") (pinfunction "2_2") (pintype "passive"))
      (node (ref "IC6") (pin "1") (pinfunction "IN_1") (pintype "input"))
      (node (ref "IC6") (pin "3") (pinfunction "EN_3") (pintype "input"))
      (node (ref "L3") (pin "2") (pinfunction "2_2") (pintype "passive"))
    )
    (net (code "35") (name "Net-(IC7-ADBUS7)") (class "Default")
      (node (ref "IC7") (pin "20") (pinfunction "ADBUS7_20") (pintype "bidirectional"))
      (node (ref "R45") (pin "1") (pinfunction "1_1") (pintype "passive"))
    )
    (net (code "36") (name "Net-(IC7-BDBUS0)") (class "Default")
      (node (ref "IC7") (pin "22") (pinfunction "BDBUS0_22") (pintype "bidirectional"))
      (node (ref "IC9") (pin "10") (pinfunction "B1_10") (pintype "bidirectional"))
    )
    (net (code "37") (name "Net-(IC7-BDBUS1)") (class "Default")
      (node (ref "IC7") (pin "23") (pinfunction "BDBUS1_23") (pintype "bidirectional"))
      (node (ref "IC9") (pin "9") (pinfunction "B2_9") (pintype "bidirectional"))
    )
    (net (code "38") (name "Net-(IC7-CDBUS0)") (class "Default")
      (node (ref "IC7") (pin "32") (pinfunction "CDBUS0_32") (pintype "bidirectional"))
      (node (ref "IC9") (pin "8") (pinfunction "B3_8") (pintype "bidirectional"))
    )
    (net (code "39") (name "Net-(IC7-CDBUS1)") (class "Default")
      (node (ref "IC7") (pin "33") (pinfunction "CDBUS1_33") (pintype "bidirectional"))
      (node (ref "IC9") (pin "7") (pinfunction "B4_7") (pintype "bidirectional"))
    )
    (net (code "40") (name "Net-(IC7-DDBUS0)") (class "Default")
      (node (ref "IC7") (pin "42") (pinfunction "DDBUS0_42") (pintype "bidirectional"))
      (node (ref "R28") (pin "1") (pinfunction "1_1") (pintype "passive"))
    )
    (net (code "41") (name "Net-(IC7-DDBUS1)") (class "Default")
      (node (ref "IC7") (pin "46") (pinfunction "DDBUS1_46") (pintype "bidirectional"))
      (node (ref "R27") (pin "1") (pinfunction "1_1") (pintype "passive"))
    )
    (net (code "42") (name "Net-(IC7-DDBUS2)") (class "Default")
      (node (ref "IC7") (pin "47") (pinfunction "DDBUS2_47") (pintype "bidirectional"))
      (node (ref "R26") (pin "1") (pinfunction "1_1") (pintype "passive"))
    )
    (net (code "43") (name "Net-(IC7-DDBUS4)") (class "Default")
      (node (ref "IC7") (pin "49") (pinfunction "DDBUS4_49") (pintype "bidirectional"))
      (node (ref "R29") (pin "1") (pinfunction "1_1") (pintype "passive"))
    )
    (net (code "44") (name "Net-(IC7-OSCI)") (class "Default")
      (node (ref "C410") (pin "2") (pinfunction "2_2") (pintype "passive"))
      (node (ref "IC7") (pin "3") (pinfunction "OSCI_3") (pintype "input"))
      (node (ref "Q1") (pin "3") (pinfunction "X_3") (pintype "passive"))
    )
    (net (code "45") (name "Net-(IC7-OSCO)") (class "Default")
      (node (ref "C409") (pin "2") (pinfunction "2_2") (pintype "passive"))
      (node (ref "IC7") (pin "4") (pinfunction "OSCO_4") (pintype "output"))
      (node (ref "Q1") (pin "1") (pinfunction "X_1") (pintype "passive"))
    )
    (net (code "46") (name "Net-(IC7-REF)") (class "Default")
      (node (ref "IC7") (pin "6") (pinfunction "REF_6") (pintype "input"))
      (node (ref "R19") (pin "2") (pinfunction "2_2") (pintype "passive"))
    )
    (net (code "47") (name "Net-(IC7-VPHY)") (class "Default")
      (node (ref "C13") (pin "2") (pinfunction "2_2") (pintype "passive"))
      (node (ref "C548") (pin "2") (pinfunction "2_2") (pintype "passive"))
      (node (ref "IC7") (pin "5") (pinfunction "VPHY_5") (pintype "power_in"))
      (node (ref "L2") (pin "2") (pinfunction "2_2") (pintype "passive"))
    )
    (net (code "48") (name "Net-(IC7-VPLL)") (class "Default")
      (node (ref "C14") (pin "2") (pinfunction "2_2") (pintype "passive"))
      (node (ref "C549") (pin "2") (pinfunction "2_2") (pintype "passive"))
      (node (ref "IC7") (pin "9") (pinfunction "VPLL_9") (pintype "power_in"))
      (node (ref "L1") (pin "2") (pinfunction "2_2") (pintype "passive"))
    )
    (net (code "49") (name "Net-(IC7-~{RESET})") (class "Default")
      (node (ref "IC7") (pin "11") (pinfunction "~{RESET}_11") (pintype "input"))
      (node (ref "R24") (pin "2") (pinfunction "2_2") (pintype "passive"))
      (node (ref "R25") (pin "2") (pinfunction "2_2") (pintype "passive"))
    )
    (net (code "50") (name "Net-(IC8-A4)") (class "Default")
      (node (ref "IC8") (pin "5") (pinfunction "A4_5") (pintype "bidirectional"))
      (node (ref "R517") (pin "2") (pinfunction "2_2") (pintype "passive"))
      (node (ref "T2") (pin "1") (pinfunction "G_1") (pintype "passive"))
    )
    (net (code "51") (name "Net-(IC8-B1)") (class "Default")
      (node (ref "IC8") (pin "10") (pinfunction "B1_10") (pintype "bidirectional"))
      (node (ref "R28") (pin "2") (pinfunction "2_2") (pintype "passive"))
    )
    (net (code "52") (name "Net-(IC8-B2)") (class "Default")
      (node (ref "IC8") (pin "9") (pinfunction "B2_9") (pintype "bidirectional"))
      (node (ref "R27") (pin "2") (pinfunction "2_2") (pintype "passive"))
    )
    (net (code "53") (name "Net-(IC8-B3)") (class "Default")
      (node (ref "IC8") (pin "8") (pinfunction "B3_8") (pintype "bidirectional"))
      (node (ref "R26") (pin "2") (pinfunction "2_2") (pintype "passive"))
      (node (ref "R34") (pin "1") (pinfunction "1_1") (pintype "passive"))
    )
    (net (code "54") (name "Net-(IC8-B4)") (class "Default")
      (node (ref "IC8") (pin "7") (pinfunction "B4_7") (pintype "bidirectional"))
      (node (ref "R29") (pin "2") (pinfunction "2_2") (pintype "passive"))
      (node (ref "R33") (pin "1") (pinfunction "1_1") (pintype "passive"))
    )
    (net (code "55") (name "Net-(IC8-OE)") (class "Default")
      (node (ref "C15") (pin "2") (pinfunction "2_2") (pintype "passive"))
      (node (ref "IC8") (pin "12") (pinfunction "OE_12") (pintype "input"))
      (node (ref "R31") (pin "1") (pinfunction "1_1") (pintype "passive"))
    )
    (net (code "56") (name "Net-(IC9-OE)") (class "Default")
      (node (ref "IC9") (pin "12") (pinfunction "OE_12") (pintype "input"))
      (node (ref "R30") (pin "1") (pinfunction "1_1") (pintype "passive"))
    )
    (net (code "57") (name "Net-(IC10-C)") (class "Default")
      (node (ref "IC10") (pin "2") (pinfunction "C_2") (pintype "input"))
      (node (ref "IC7") (pin "56") (pinfunction "EECLK_56") (pintype "output"))
      (node (ref "R22") (pin "1") (pinfunction "1_1") (pintype "passive"))
    )
    (net (code "58") (name "Net-(IC10-D)") (class "Default")
      (node (ref "IC10") (pin "3") (pinfunction "D_3") (pintype "input"))
      (node (ref "IC7") (pin "55") (pinfunction "EEDATA_55") (pintype "bidirectional"))
      (node (ref "R21") (pin "2") (pinfunction "2_2") (pintype "passive"))
    )
    (net (code "59") (name "Net-(IC10-Q)") (class "Default")
      (node (ref "IC10") (pin "4") (pinfunction "Q_4") (pintype "output"))
      (node (ref "R20") (pin "1") (pinfunction "1_1") (pintype "passive"))
      (node (ref "R21") (pin "1") (pinfunction "1_1") (pintype "passive"))
    )
    (net (code "60") (name "Net-(IC10-S)") (class "Default")
      (node (ref "IC10") (pin "1") (pinfunction "S_1") (pintype "input"))
      (node (ref "IC7") (pin "1") (pinfunction "EECS_1") (pintype "bidirectional"))
      (node (ref "R23") (pin "1") (pinfunction "1_1") (pintype "passive"))
    )
    (net (code "61") (name "Net-(IC11-~{OE})") (class "Default")
      (node (ref "IC11") (pin "2") (pinfunction "~{OE}_2") (pintype "input"))
      (node (ref "IC12") (pin "2") (pinfunction "~{OE}_2") (pintype "input"))
      (node (ref "R39") (pin "1") (pinfunction "1_1") (pintype "passive"))
      (node (ref "T3") (pin "3") (pinfunction "D_3") (pintype "passive"))
    )
    (net (code "62") (name "Net-(T1-G)") (class "Default")
      (node (ref "R44") (pin "2") (pinfunction "2_2") (pintype "passive"))
      (node (ref "T1") (pin "1") (pinfunction "G_1") (pintype "passive"))
    )
    (net (code "63") (name "Net-(T1-S)") (class "Default")
      (node (ref "T1") (pin "2") (pinfunction "S_2") (pintype "passive"))
      (node (ref "T4") (pin "3") (pinfunction "D_3") (pintype "passive"))
    )
    (net (code "64") (name "Net-(T2-D)") (class "Default")
      (node (ref "R32") (pin "1") (pinfunction "1_1") (pintype "passive"))
      (node (ref "R44") (pin "1") (pinfunction "1_1") (pintype "passive"))
      (node (ref "T2") (pin "3") (pinfunction "D_3") (pintype "passive"))
    )
    (net (code "65") (name "P1V8_USB") (class "Default")
      (node (ref "C10") (pin "2") (pinfunction "2_2") (pintype "passive"))
      (node (ref "C408") (pin "1") (pinfunction "1_1") (pintype "passive"))
      (node (ref "C547") (pin "1") (pinfunction "1_1") (pintype "passive"))
      (node (ref "C7") (pin "2") (pinfunction "2_2") (pintype "passive"))
      (node (ref "C8") (pin "2") (pinfunction "2_2") (pintype "passive"))
      (node (ref "C9") (pin "2") (pinfunction "2_2") (pintype "passive"))
      (node (ref "IC7") (pin "2") (pinfunction "VCORE_2") (pintype "power_in"))
      (node (ref "IC7") (pin "31") (pinfunction "VCORE_31") (pintype "power_in"))
      (node (ref "IC7") (pin "43") (pinfunction "VREGOUT_43") (pintype "output"))
    )
    (net (code "66") (name "P3V3") (class "Default")
      (node (ref "C16") (pin "2") (pinfunction "2_2") (pintype "passive"))
      (node (ref "C19") (pin "2") (pinfunction "2_2") (pintype "passive"))
      (node (ref "C20") (pin "2") (pinfunction "2_2") (pintype "passive"))
      (node (ref "C532") (pin "2") (pinfunction "2_2") (pintype "passive"))
      (node (ref "IC11") (pin "6") (pinfunction "VCCB_6") (pintype "power_in"))
      (node (ref "IC12") (pin "6") (pinfunction "VCCB_6") (pintype "power_in"))
      (node (ref "IC9") (pin "1") (pinfunction "VCCA_1") (pintype "power_in"))
    )
    (net (code "67") (name "P3V3MP") (class "Default")
      (node (ref "IC8") (pin "1") (pinfunction "VCCA_1") (pintype "power_in"))
      (node (ref "R517") (pin "1") (pinfunction "1_1") (pintype "passive"))
      (node (ref "R518") (pin "2") (pinfunction "2_2") (pintype "passive"))
    )
    (net (code "68") (name "P3V3_USB") (class "Default")
      (node (ref "C11") (pin "2") (pinfunction "2_2") (pintype "passive"))
      (node (ref "C17") (pin "2") (pinfunction "2_2") (pintype "passive"))
      (node (ref "C18") (pin "2") (pinfunction "2_2") (pintype "passive"))
      (node (ref "C3") (pin "2") (pinfunction "2_2") (pintype "passive"))
      (node (ref "C4") (pin "2") (pinfunction "2_2") (pintype "passive"))
      (node (ref "C406") (pin "1") (pinfunction "1_1") (pintype "passive"))
      (node (ref "C5") (pin "2") (pinfunction "2_2") (pintype "passive"))
      (node (ref "C6") (pin "2") (pinfunction "2_2") (pintype "passive"))
      (node (ref "D2") (pin "1") (pinfunction "C_1") (pintype "passive"))
      (node (ref "IC10") (pin "6") (pinfunction "ORG_6") (pintype "input"))
      (node (ref "IC10") (pin "8") (pinfunction "VCC_8") (pintype "power_in"))
      (node (ref "IC11") (pin "1") (pinfunction "DIR2_1") (pintype "input"))
      (node (ref "IC11") (pin "10") (pinfunction "DIR1_10") (pintype "input"))
      (node (ref "IC11") (pin "7") (pinfunction "VCCA_7") (pintype "power_in"))
      (node (ref "IC12") (pin "10") (pinfunction "DIR1_10") (pintype "input"))
      (node (ref "IC12") (pin "7") (pinfunction "VCCA_7") (pintype "power_in"))
      (node (ref "IC6") (pin "5") (pinfunction "OUT_5") (pintype "power_in"))
      (node (ref "IC7") (pin "16") (pinfunction "VCCIO_16") (pintype "power_in"))
      (node (ref "IC7") (pin "36") (pinfunction "VCCIO_36") (pintype "power_in"))
      (node (ref "IC7") (pin "44") (pinfunction "VREGIN_44") (pintype "input"))
      (node (ref "IC7") (pin "50") (pinfunction "VCCIO_50") (pintype "power_in"))
      (node (ref "IC8") (pin "11") (pinfunction "VCCB_11") (pintype "power_in"))
      (node (ref "IC9") (pin "11") (pinfunction "VCCB_11") (pintype "power_in"))
      (node (ref "L1") (pin "1") (pinfunction "1_1") (pintype "passive"))
      (node (ref "L2") (pin "1") (pinfunction "1_1") (pintype "passive"))
      (node (ref "R20") (pin "2") (pinfunction "2_2") (pintype "passive"))
      (node (ref "R22") (pin "2") (pinfunction "2_2") (pintype "passive"))
      (node (ref "R23") (pin "2") (pinfunction "2_2") (pintype "passive"))
      (node (ref "R30") (pin "2") (pinfunction "2_2") (pintype "passive"))
      (node (ref "R31") (pin "2") (pinfunction "2_2") (pintype "passive"))
      (node (ref "R32") (pin "2") (pinfunction "2_2") (pintype "passive"))
      (node (ref "R33") (pin "2") (pinfunction "2_2") (pintype "passive"))
      (node (ref "R34") (pin "2") (pinfunction "2_2") (pintype "passive"))
      (node (ref "R35") (pin "1") (pinfunction "1_1") (pintype "passive"))
      (node (ref "R36") (pin "1") (pinfunction "1_1") (pintype "passive"))
      (node (ref "R37") (pin "1") (pinfunction "1_1") (pintype "passive"))
      (node (ref "R38") (pin "1") (pinfunction "1_1") (pintype "passive"))
      (node (ref "R39") (pin "2") (pinfunction "2_2") (pintype "passive"))
      (node (ref "R42") (pin "1") (pinfunction "1_1") (pintype "passive"))
      (node (ref "R43") (pin "2") (pinfunction "2_2") (pintype "passive"))
    )
    (net (code "69") (name "unconnected-(IC6-BYP-Pad4)") (class "Default")
      (node (ref "IC6") (pin "4") (pinfunction "BYP_4") (pintype "passive"))
    )
    (net (code "70") (name "unconnected-(IC7-ADBUS4-Pad17)") (class "Default")
      (node (ref "IC7") (pin "17") (pinfunction "ADBUS4_17") (pintype "bidirectional+no_connect"))
    )
    (net (code "71") (name "unconnected-(IC7-ADBUS5-Pad18)") (class "Default")
      (node (ref "IC7") (pin "18") (pinfunction "ADBUS5_18") (pintype "bidirectional+no_connect"))
    )
    (net (code "72") (name "unconnected-(IC7-ADBUS6-Pad19)") (class "Default")
      (node (ref "IC7") (pin "19") (pinfunction "ADBUS6_19") (pintype "bidirectional+no_connect"))
    )
    (net (code "73") (name "unconnected-(IC7-BDBUS2-Pad24)") (class "Default")
      (node (ref "IC7") (pin "24") (pinfunction "BDBUS2_24") (pintype "bidirectional+no_connect"))
    )
    (net (code "74") (name "unconnected-(IC7-BDBUS3-Pad25)") (class "Default")
      (node (ref "IC7") (pin "25") (pinfunction "BDBUS3_25") (pintype "bidirectional+no_connect"))
    )
    (net (code "75") (name "unconnected-(IC7-BDBUS4-Pad26)") (class "Default")
      (node (ref "IC7") (pin "26") (pinfunction "BDBUS4_26") (pintype "bidirectional+no_connect"))
    )
    (net (code "76") (name "unconnected-(IC7-BDBUS5-Pad27)") (class "Default")
      (node (ref "IC7") (pin "27") (pinfunction "BDBUS5_27") (pintype "bidirectional+no_connect"))
    )
    (net (code "77") (name "unconnected-(IC7-BDBUS6-Pad28)") (class "Default")
      (node (ref "IC7") (pin "28") (pinfunction "BDBUS6_28") (pintype "bidirectional+no_connect"))
    )
    (net (code "78") (name "unconnected-(IC7-BDBUS7-Pad29)") (class "Default")
      (node (ref "IC7") (pin "29") (pinfunction "BDBUS7_29") (pintype "bidirectional+no_connect"))
    )
    (net (code "79") (name "unconnected-(IC7-CDBUS2-Pad34)") (class "Default")
      (node (ref "IC7") (pin "34") (pinfunction "CDBUS2_34") (pintype "bidirectional+no_connect"))
    )
    (net (code "80") (name "unconnected-(IC7-CDBUS3-Pad35)") (class "Default")
      (node (ref "IC7") (pin "35") (pinfunction "CDBUS3_35") (pintype "bidirectional+no_connect"))
    )
    (net (code "81") (name "unconnected-(IC7-CDBUS4-Pad37)") (class "Default")
      (node (ref "IC7") (pin "37") (pinfunction "CDBUS4_37") (pintype "bidirectional+no_connect"))
    )
    (net (code "82") (name "unconnected-(IC7-CDBUS5-Pad38)") (class "Default")
      (node (ref "IC7") (pin "38") (pinfunction "CDBUS5_38") (pintype "bidirectional+no_connect"))
    )
    (net (code "83") (name "unconnected-(IC7-CDBUS6-Pad39)") (class "Default")
      (node (ref "IC7") (pin "39") (pinfunction "CDBUS6_39") (pintype "bidirectional+no_connect"))
    )
    (net (code "84") (name "unconnected-(IC7-CDBUS7-Pad40)") (class "Default")
      (node (ref "IC7") (pin "40") (pinfunction "CDBUS7_40") (pintype "bidirectional+no_connect"))
    )
    (net (code "85") (name "unconnected-(IC7-DDBUS3-Pad48)") (class "Default")
      (node (ref "IC7") (pin "48") (pinfunction "DDBUS3_48") (pintype "bidirectional+no_connect"))
    )
    (net (code "86") (name "unconnected-(IC7-DDBUS5-Pad51)") (class "Default")
      (node (ref "IC7") (pin "51") (pinfunction "DDBUS5_51") (pintype "bidirectional+no_connect"))
    )
    (net (code "87") (name "unconnected-(IC7-DDBUS6-Pad52)") (class "Default")
      (node (ref "IC7") (pin "52") (pinfunction "DDBUS6_52") (pintype "bidirectional+no_connect"))
    )
    (net (code "88") (name "unconnected-(IC7-DDBUS7-Pad53)") (class "Default")
      (node (ref "IC7") (pin "53") (pinfunction "DDBUS7_53") (pintype "bidirectional+no_connect"))
    )
    (net (code "89") (name "unconnected-(IC7-~{PWREN}-Pad54)") (class "Default")
      (node (ref "IC7") (pin "54") (pinfunction "~{PWREN}_54") (pintype "output+no_connect"))
    )
    (net (code "90") (name "unconnected-(IC7-~{SUSPEND}-Pad30)") (class "Default")
      (node (ref "IC7") (pin "30") (pinfunction "~{SUSPEND}_30") (pintype "output+no_connect"))
    )
    (net (code "91") (name "unconnected-(IC10-DU-Pad7)") (class "Default")
      (node (ref "IC10") (pin "7") (pinfunction "DU_7") (pintype "passive"))
    )
    (net (code "92") (name "unconnected-(J4-ID-Pad4)") (class "Default")
      (node (ref "J4") (pin "4") (pinfunction "ID_4") (pintype "passive"))
    )
  )
)
